# EMatches.net
KiCad netlist of a schematic drawn in Altium Designer
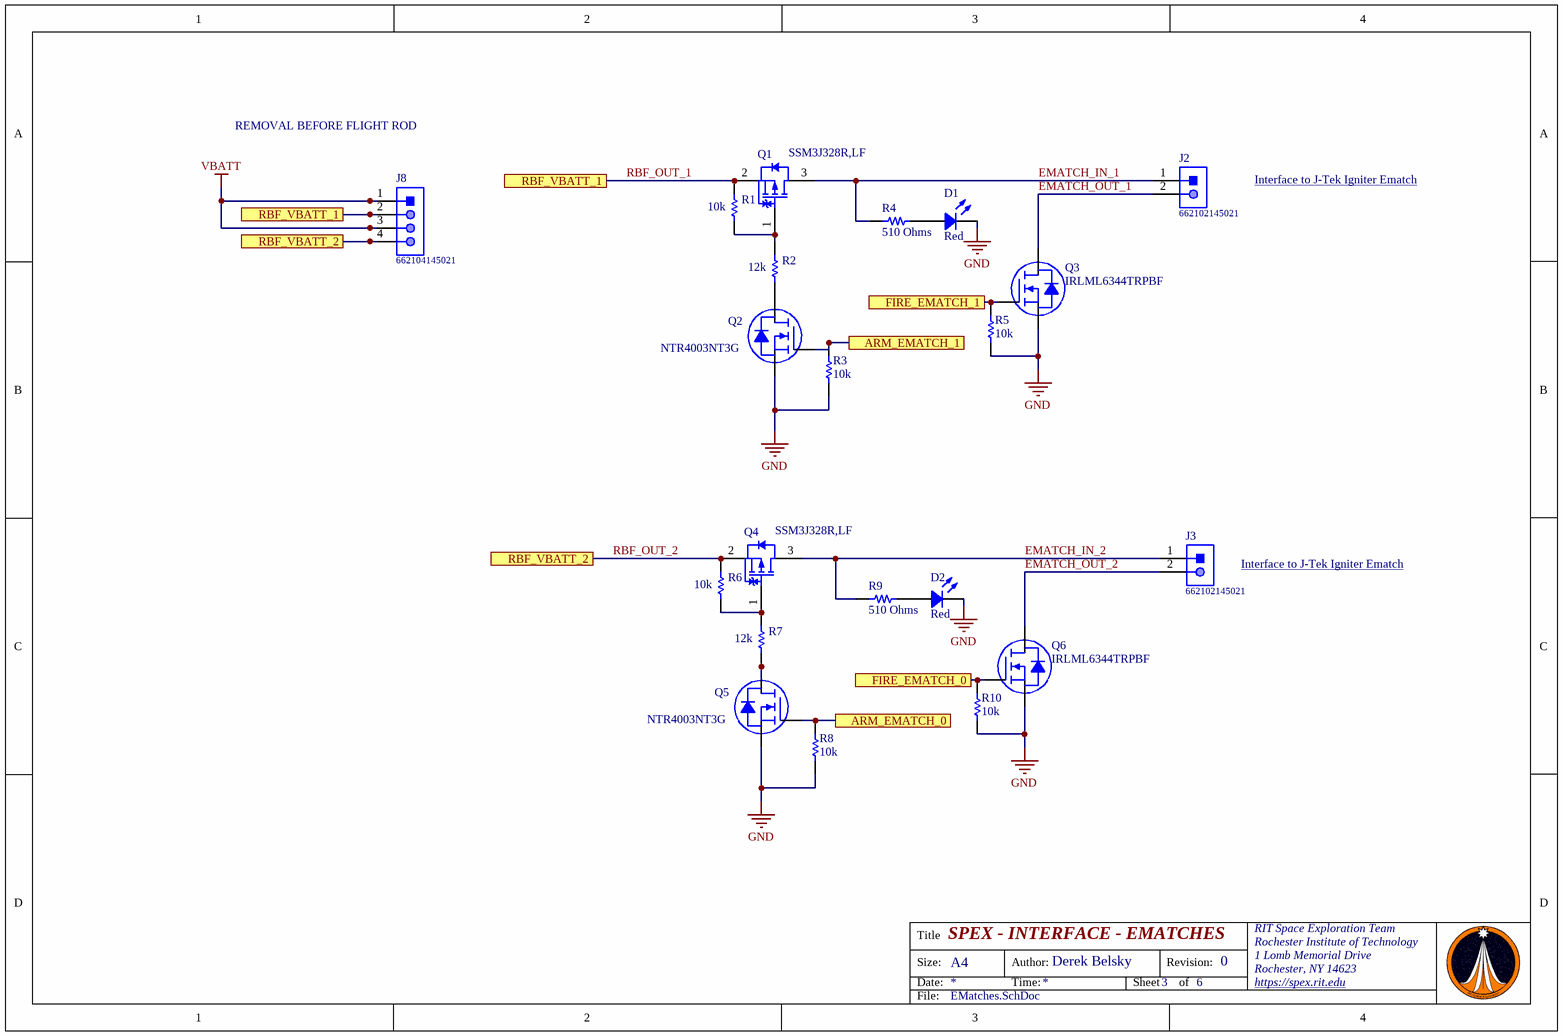
[diagram p0: EMatches.SchDoc]

(export (version "E")
  (design (tool "Eeschema 10.0.6"))
  (components
    (comp (ref "D1")
      (value "Red")
      (footprint "LED 1206_3216 RED")
      (description "LED RED CHIP SMD")
      (fields (field (name "PART NUMBER") "HSMC-C350") (field (name "MANUFACTURER") "Broadcom Limited"))
      (libsource (lib "Celestial Altium Library - altium_library") (part "LED"))
    )
    (comp (ref "D2")
      (value "Red")
      (footprint "LED 1206_3216 RED")
      (description "LED RED CHIP SMD")
      (fields (field (name "PART NUMBER") "HSMC-C350") (field (name "MANUFACTURER") "Broadcom Limited"))
      (libsource (lib "Celestial Altium Library - altium_library") (part "LED"))
    )
    (comp (ref "J2")
      (value "662102145021")
      (footprint "662102145021")
      (description "SMT Male Header WR-MPC3, with SMT Solder Tabs, Right Angled, Single Row, pitch 3 mm, 2 pins")
      (fields (field (name "MANUFACTURER") "Wurth Elektronik") (field (name "PUBLISHER") "WurthElektronik"))
      (libsource (lib "Altium Content Vault") (part "WE-CN-1P-M-R2"))
    )
    (comp (ref "J3")
      (value "662102145021")
      (footprint "662102145021")
      (description "SMT Male Header WR-MPC3, with SMT Solder Tabs, Right Angled, Single Row, pitch 3 mm, 2 pins")
      (fields (field (name "MANUFACTURER") "Wurth Elektronik") (field (name "PUBLISHER") "WurthElektronik"))
      (libsource (lib "Altium Content Vault") (part "WE-CN-1P-M-R2"))
    )
    (comp (ref "J8")
      (value "662104145021")
      (footprint "662104145021")
      (description "SMT Male Header WR-MPC3, with SMT Solder Tabs, Right Angled, Single Row, pitch 3 mm, 4 pins")
      (fields (field (name "MANUFACTURER") "Wurth Elektronik") (field (name "PUBLISHER") "WurthElektronik"))
      (libsource (lib "Altium Content Vault") (part "WE-CN-1P-M-R4"))
    )
    (comp (ref "Q1")
      (value "SSM3J328R,LF")
      (footprint "TOSH-SOT-23F_V")
      (fields (field (name "MANUFACTURER") "Toshiba"))
      (libsource (lib "Altium Content Vault") (part "PEMOS-GSD-3_C"))
    )
    (comp (ref "Q2")
      (value "NTR4003NT3G")
      (footprint "ON SEMI SOT-23-3")
      (description "MOSFET N-CH 30V 500MA SOT-23")
      (fields (field (name "MANUFACTURER") "ON Semiconductor"))
      (libsource (lib "Celestial Altium Library - altium_library") (part "ON SEMI MOSFET N-CH SOT-23-3"))
    )
    (comp (ref "Q3")
      (value "IRLML6344TRPBF")
      (footprint "INFINEON SOT-23-3")
      (description "MOSFET N-CH 30V 5A SOT23")
      (fields (field (name "MANUFACTURER") "Infineon Technologies"))
      (libsource (lib "Celestial Altium Library - altium_library") (part "INFINEON MOSFET N-CH SOT-23-3 GSD"))
    )
    (comp (ref "Q4")
      (value "SSM3J328R,LF")
      (footprint "TOSH-SOT-23F_V")
      (fields (field (name "MANUFACTURER") "Toshiba"))
      (libsource (lib "Altium Content Vault") (part "PEMOS-GSD-3_C"))
    )
    (comp (ref "Q5")
      (value "NTR4003NT3G")
      (footprint "ON SEMI SOT-23-3")
      (description "MOSFET N-CH 30V 500MA SOT-23")
      (fields (field (name "MANUFACTURER") "ON Semiconductor"))
      (libsource (lib "Celestial Altium Library - altium_library") (part "ON SEMI MOSFET N-CH SOT-23-3"))
    )
    (comp (ref "Q6")
      (value "IRLML6344TRPBF")
      (footprint "INFINEON SOT-23-3")
      (description "MOSFET N-CH 30V 5A SOT23")
      (fields (field (name "MANUFACTURER") "Infineon Technologies"))
      (libsource (lib "Celestial Altium Library - altium_library") (part "INFINEON MOSFET N-CH SOT-23-3 GSD"))
    )
    (comp (ref "R1")
      (value "10k")
      (footprint "RESC1609X50X30NL8T20")
      (description "Chip Resistor, 10 KOhm, +/- 1%, 100 mW, -55 to 155 degC, 0603 (1608 Metric), RoHS, Tape and Reel")
      (fields
        (field (name "MANUFACTURER") "Vishay Semiconductor")
        (field (name "Comment") "CRCW060310K0FKEA")
      )
      (libsource (lib "Altium Content Vault") (part "RES-2"))
    )
    (comp (ref "R2")
      (value "12k")
      (footprint "RESC1609X50X30LL10T20")
      (fields (field (name "MANUFACTURER") "Vishay Dale") (field (name "PART NUMBER") "CRCW060312K0FKEA"))
      (libsource (lib "Altium Content Vault") (part "RES"))
    )
    (comp (ref "R3")
      (value "10k")
      (footprint "RESC1609X50X30NL8T20")
      (description "Chip Resistor, 10 KOhm, +/- 1%, 100 mW, -55 to 155 degC, 0603 (1608 Metric), RoHS, Tape and Reel")
      (fields
        (field (name "MANUFACTURER") "Vishay Semiconductor")
        (field (name "Comment") "CRCW060310K0FKEA")
      )
      (libsource (lib "Altium Content Vault") (part "RES-2"))
    )
    (comp (ref "R4")
      (value "510 Ohms")
      (footprint "RES 0603_1608")
      (description "RES SMD 510 OHM 1% 1/4W 0603")
      (fields (field (name "PART NUMBER") "CRCW0603510RFKEAHP") (field (name "MANUFACTURER") "Vishay Dale"))
      (libsource (lib "Celestial Altium Library - altium_library") (part "Resistor"))
    )
    (comp (ref "R5")
      (value "10k")
      (footprint "RESC1609X50X30NL8T20")
      (description "Chip Resistor, 10 KOhm, +/- 1%, 100 mW, -55 to 155 degC, 0603 (1608 Metric), RoHS, Tape and Reel")
      (fields
        (field (name "MANUFACTURER") "Vishay Semiconductor")
        (field (name "Comment") "CRCW060310K0FKEA")
      )
      (libsource (lib "Altium Content Vault") (part "RES-2"))
    )
    (comp (ref "R6")
      (value "10k")
      (footprint "RESC1609X50X30NL8T20")
      (description "Chip Resistor, 10 KOhm, +/- 1%, 100 mW, -55 to 155 degC, 0603 (1608 Metric), RoHS, Tape and Reel")
      (fields
        (field (name "MANUFACTURER") "Vishay Semiconductor")
        (field (name "Comment") "CRCW060310K0FKEA")
      )
      (libsource (lib "Altium Content Vault") (part "RES-2"))
    )
    (comp (ref "R7")
      (value "12k")
      (footprint "RESC1609X50X30LL10T20")
      (fields (field (name "MANUFACTURER") "Vishay Dale") (field (name "PART NUMBER") "CRCW060312K0FKEA"))
      (libsource (lib "Altium Content Vault") (part "RES"))
    )
    (comp (ref "R8")
      (value "10k")
      (footprint "RESC1609X50X30NL8T20")
      (description "Chip Resistor, 10 KOhm, +/- 1%, 100 mW, -55 to 155 degC, 0603 (1608 Metric), RoHS, Tape and Reel")
      (fields
        (field (name "MANUFACTURER") "Vishay Semiconductor")
        (field (name "Comment") "CRCW060310K0FKEA")
      )
      (libsource (lib "Altium Content Vault") (part "RES-2"))
    )
    (comp (ref "R9")
      (value "510 Ohms")
      (footprint "RES 0603_1608")
      (description "RES SMD 510 OHM 1% 1/4W 0603")
      (fields (field (name "PART NUMBER") "CRCW0603510RFKEAHP") (field (name "MANUFACTURER") "Vishay Dale"))
      (libsource (lib "Celestial Altium Library - altium_library") (part "Resistor"))
    )
    (comp (ref "R10")
      (value "10k")
      (footprint "RESC1609X50X30NL8T20")
      (description "Chip Resistor, 10 KOhm, +/- 1%, 100 mW, -55 to 155 degC, 0603 (1608 Metric), RoHS, Tape and Reel")
      (fields
        (field (name "MANUFACTURER") "Vishay Semiconductor")
        (field (name "Comment") "CRCW060310K0FKEA")
      )
      (libsource (lib "Altium Content Vault") (part "RES-2"))
    )
  )
  (nets
    (net (code "1") (name "/ARM_EMATCH_0") (class "Default")
      (node (ref "Q5") (pin "1") (pinfunction "G_1") (pintype "passive"))
      (node (ref "R8") (pin "1") (pinfunction "1_1") (pintype "passive"))
    )
    (net (code "2") (name "/ARM_EMATCH_1") (class "Default")
      (node (ref "Q2") (pin "1") (pinfunction "G_1") (pintype "passive"))
      (node (ref "R3") (pin "1") (pinfunction "1_1") (pintype "passive"))
    )
    (net (code "3") (name "/EMATCH_IN_1") (class "Default")
      (node (ref "J2") (pin "1") (pinfunction "1_1") (pintype "passive"))
      (node (ref "Q1") (pin "3") (pinfunction "D_3") (pintype "passive"))
      (node (ref "R4") (pin "1") (pinfunction "1_1") (pintype "passive"))
    )
    (net (code "4") (name "/EMATCH_IN_2") (class "Default")
      (node (ref "J3") (pin "1") (pinfunction "1_1") (pintype "passive"))
      (node (ref "Q4") (pin "3") (pinfunction "D_3") (pintype "passive"))
      (node (ref "R9") (pin "1") (pinfunction "1_1") (pintype "passive"))
    )
    (net (code "5") (name "/EMATCH_OUT_1") (class "Default")
      (node (ref "J2") (pin "2") (pinfunction "2_2") (pintype "passive"))
      (node (ref "Q3") (pin "3") (pinfunction "D_3") (pintype "passive"))
    )
    (net (code "6") (name "/EMATCH_OUT_2") (class "Default")
      (node (ref "J3") (pin "2") (pinfunction "2_2") (pintype "passive"))
      (node (ref "Q6") (pin "3") (pinfunction "D_3") (pintype "passive"))
    )
    (net (code "7") (name "/FIRE_EMATCH_0") (class "Default")
      (node (ref "Q6") (pin "1") (pinfunction "G_1") (pintype "passive"))
      (node (ref "R10") (pin "1") (pinfunction "1_1") (pintype "passive"))
    )
    (net (code "8") (name "/FIRE_EMATCH_1") (class "Default")
      (node (ref "Q3") (pin "1") (pinfunction "G_1") (pintype "passive"))
      (node (ref "R5") (pin "1") (pinfunction "1_1") (pintype "passive"))
    )
    (net (code "9") (name "/RBF_OUT_1") (class "Default")
      (node (ref "J8") (pin "2") (pinfunction "2_2") (pintype "passive"))
      (node (ref "Q1") (pin "2") (pinfunction "S_2") (pintype "passive"))
      (node (ref "R1") (pin "2") (pinfunction "2_2") (pintype "passive"))
    )
    (net (code "10") (name "/RBF_OUT_2") (class "Default")
      (node (ref "J8") (pin "4") (pinfunction "4_4") (pintype "passive"))
      (node (ref "Q4") (pin "2") (pinfunction "S_2") (pintype "passive"))
      (node (ref "R6") (pin "2") (pinfunction "2_2") (pintype "passive"))
    )
    (net (code "11") (name "GND") (class "Default")
      (node (ref "D1") (pin "2") (pinfunction "2_2") (pintype "passive"))
      (node (ref "D2") (pin "2") (pinfunction "2_2") (pintype "passive"))
      (node (ref "Q2") (pin "2") (pinfunction "S_2") (pintype "passive"))
      (node (ref "Q3") (pin "2") (pinfunction "S_2") (pintype "passive"))
      (node (ref "Q5") (pin "2") (pinfunction "S_2") (pintype "passive"))
      (node (ref "Q6") (pin "2") (pinfunction "S_2") (pintype "passive"))
      (node (ref "R10") (pin "2") (pinfunction "2_2") (pintype "passive"))
      (node (ref "R3") (pin "2") (pinfunction "2_2") (pintype "passive"))
      (node (ref "R5") (pin "2") (pinfunction "2_2") (pintype "passive"))
      (node (ref "R8") (pin "2") (pinfunction "2_2") (pintype "passive"))
    )
    (net (code "12") (name "Net-(D1-Pad1)") (class "Default")
      (node (ref "D1") (pin "1") (pinfunction "1_1") (pintype "passive"))
      (node (ref "R4") (pin "2") (pinfunction "2_2") (pintype "passive"))
    )
    (net (code "13") (name "Net-(D2-Pad1)") (class "Default")
      (node (ref "D2") (pin "1") (pinfunction "1_1") (pintype "passive"))
      (node (ref "R9") (pin "2") (pinfunction "2_2") (pintype "passive"))
    )
    (net (code "14") (name "Net-(Q1-G)") (class "Default")
      (node (ref "Q1") (pin "1") (pinfunction "G_1") (pintype "passive"))
      (node (ref "R1") (pin "1") (pinfunction "1_1") (pintype "passive"))
      (node (ref "R2") (pin "2") (pinfunction "2_2") (pintype "passive"))
    )
    (net (code "15") (name "Net-(Q2-D)") (class "Default")
      (node (ref "Q2") (pin "3") (pinfunction "D_3") (pintype "passive"))
      (node (ref "R2") (pin "1") (pinfunction "1_1") (pintype "passive"))
    )
    (net (code "16") (name "Net-(Q4-G)") (class "Default")
      (node (ref "Q4") (pin "1") (pinfunction "G_1") (pintype "passive"))
      (node (ref "R6") (pin "1") (pinfunction "1_1") (pintype "passive"))
      (node (ref "R7") (pin "2") (pinfunction "2_2") (pintype "passive"))
    )
    (net (code "17") (name "Net-(Q5-D)") (class "Default")
      (node (ref "Q5") (pin "3") (pinfunction "D_3") (pintype "passive"))
      (node (ref "R7") (pin "1") (pinfunction "1_1") (pintype "passive"))
    )
    (net (code "18") (name "VBATT") (class "Default")
      (node (ref "J8") (pin "1") (pinfunction "1_1") (pintype "passive"))
      (node (ref "J8") (pin "3") (pinfunction "3_3") (pintype "passive"))
    )
  )
)
